# 2pix.net
KiCad netlist of a schematic drawn in EAGLE
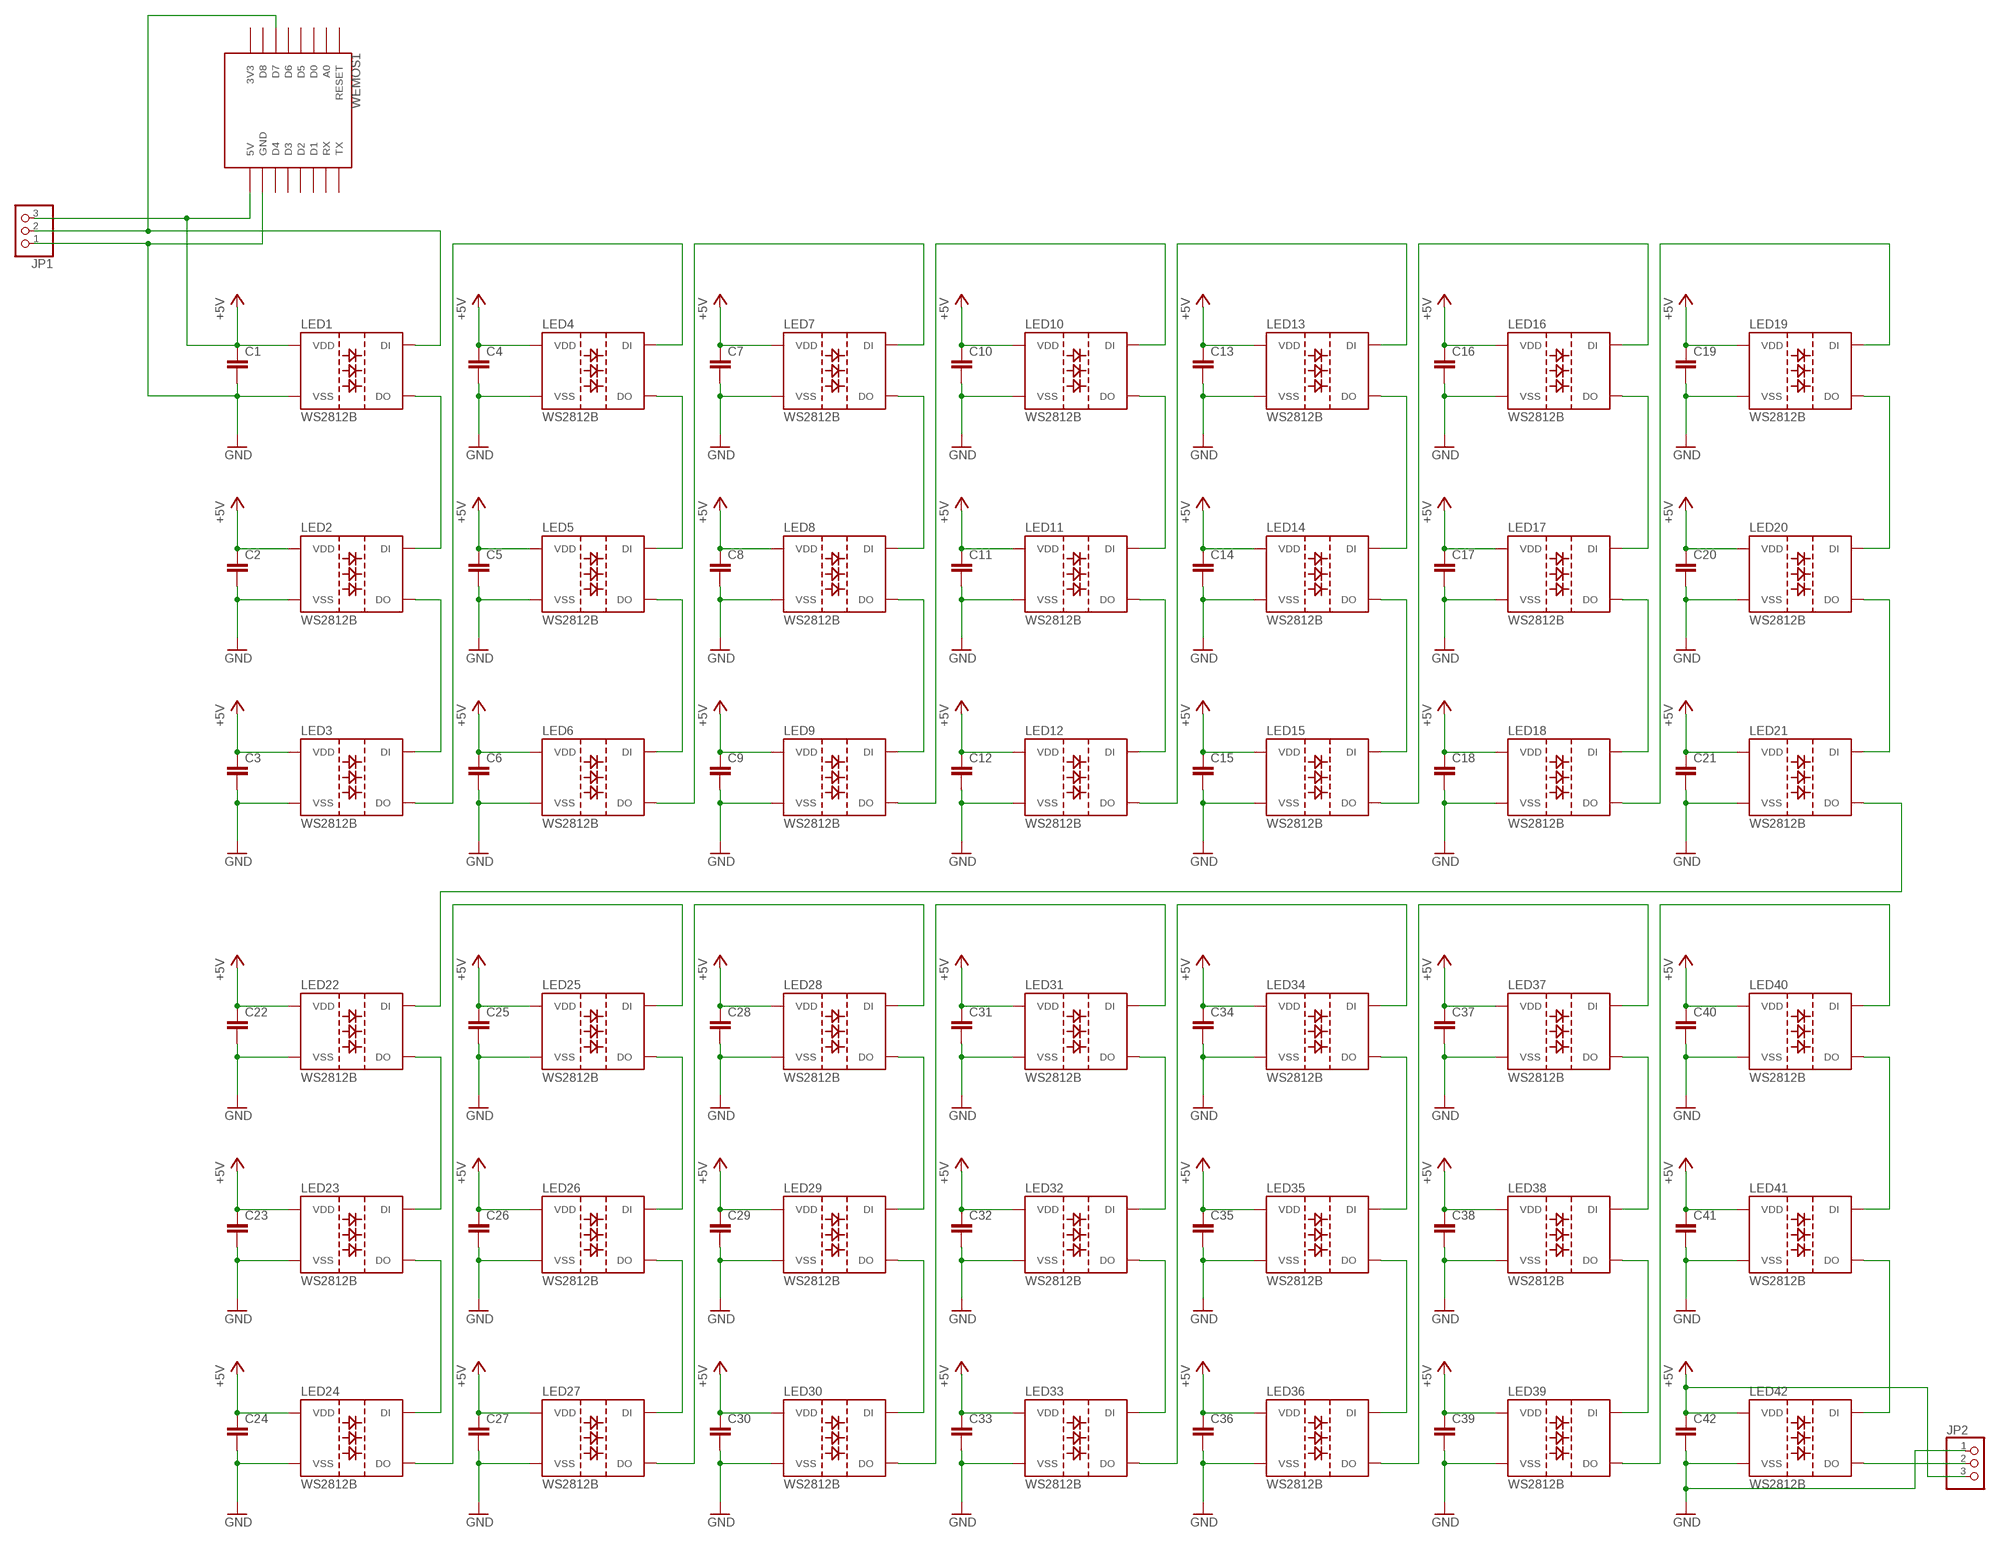
[diagram p0: schematic, sheet 1]

(export (version "E")
  (design (tool "Eeschema 10.0.6"))
  (components
    (comp (ref "C1")
      (value "C-EUC1206")
      (footprint "eagle-import:C1206")
      (libsource (lib "eagle-import") (part "C-EUC1206"))
    )
    (comp (ref "C2")
      (value "C-EUC1206")
      (footprint "eagle-import:C1206")
      (libsource (lib "eagle-import") (part "C-EUC1206"))
    )
    (comp (ref "C3")
      (value "C-EUC1206")
      (footprint "eagle-import:C1206")
      (libsource (lib "eagle-import") (part "C-EUC1206"))
    )
    (comp (ref "C4")
      (value "C-EUC1206")
      (footprint "eagle-import:C1206")
      (libsource (lib "eagle-import") (part "C-EUC1206"))
    )
    (comp (ref "C5")
      (value "C-EUC1206")
      (footprint "eagle-import:C1206")
      (libsource (lib "eagle-import") (part "C-EUC1206"))
    )
    (comp (ref "C6")
      (value "C-EUC1206")
      (footprint "eagle-import:C1206")
      (libsource (lib "eagle-import") (part "C-EUC1206"))
    )
    (comp (ref "C7")
      (value "C-EUC1206")
      (footprint "eagle-import:C1206")
      (libsource (lib "eagle-import") (part "C-EUC1206"))
    )
    (comp (ref "C8")
      (value "C-EUC1206")
      (footprint "eagle-import:C1206")
      (libsource (lib "eagle-import") (part "C-EUC1206"))
    )
    (comp (ref "C9")
      (value "C-EUC1206")
      (footprint "eagle-import:C1206")
      (libsource (lib "eagle-import") (part "C-EUC1206"))
    )
    (comp (ref "C10")
      (value "C-EUC1206")
      (footprint "eagle-import:C1206")
      (libsource (lib "eagle-import") (part "C-EUC1206"))
    )
    (comp (ref "C11")
      (value "C-EUC1206")
      (footprint "eagle-import:C1206")
      (libsource (lib "eagle-import") (part "C-EUC1206"))
    )
    (comp (ref "C12")
      (value "C-EUC1206")
      (footprint "eagle-import:C1206")
      (libsource (lib "eagle-import") (part "C-EUC1206"))
    )
    (comp (ref "C13")
      (value "C-EUC1206")
      (footprint "eagle-import:C1206")
      (libsource (lib "eagle-import") (part "C-EUC1206"))
    )
    (comp (ref "C14")
      (value "C-EUC1206")
      (footprint "eagle-import:C1206")
      (libsource (lib "eagle-import") (part "C-EUC1206"))
    )
    (comp (ref "C15")
      (value "C-EUC1206")
      (footprint "eagle-import:C1206")
      (libsource (lib "eagle-import") (part "C-EUC1206"))
    )
    (comp (ref "C16")
      (value "C-EUC1206")
      (footprint "eagle-import:C1206")
      (libsource (lib "eagle-import") (part "C-EUC1206"))
    )
    (comp (ref "C17")
      (value "C-EUC1206")
      (footprint "eagle-import:C1206")
      (libsource (lib "eagle-import") (part "C-EUC1206"))
    )
    (comp (ref "C18")
      (value "C-EUC1206")
      (footprint "eagle-import:C1206")
      (libsource (lib "eagle-import") (part "C-EUC1206"))
    )
    (comp (ref "C19")
      (value "C-EUC1206")
      (footprint "eagle-import:C1206")
      (libsource (lib "eagle-import") (part "C-EUC1206"))
    )
    (comp (ref "C20")
      (value "C-EUC1206")
      (footprint "eagle-import:C1206")
      (libsource (lib "eagle-import") (part "C-EUC1206"))
    )
    (comp (ref "C21")
      (value "C-EUC1206")
      (footprint "eagle-import:C1206")
      (libsource (lib "eagle-import") (part "C-EUC1206"))
    )
    (comp (ref "C22")
      (value "C-EUC1206")
      (footprint "eagle-import:C1206")
      (libsource (lib "eagle-import") (part "C-EUC1206"))
    )
    (comp (ref "C23")
      (value "C-EUC1206")
      (footprint "eagle-import:C1206")
      (libsource (lib "eagle-import") (part "C-EUC1206"))
    )
    (comp (ref "C24")
      (value "C-EUC1206")
      (footprint "eagle-import:C1206")
      (libsource (lib "eagle-import") (part "C-EUC1206"))
    )
    (comp (ref "C25")
      (value "C-EUC1206")
      (footprint "eagle-import:C1206")
      (libsource (lib "eagle-import") (part "C-EUC1206"))
    )
    (comp (ref "C26")
      (value "C-EUC1206")
      (footprint "eagle-import:C1206")
      (libsource (lib "eagle-import") (part "C-EUC1206"))
    )
    (comp (ref "C27")
      (value "C-EUC1206")
      (footprint "eagle-import:C1206")
      (libsource (lib "eagle-import") (part "C-EUC1206"))
    )
    (comp (ref "C28")
      (value "C-EUC1206")
      (footprint "eagle-import:C1206")
      (libsource (lib "eagle-import") (part "C-EUC1206"))
    )
    (comp (ref "C29")
      (value "C-EUC1206")
      (footprint "eagle-import:C1206")
      (libsource (lib "eagle-import") (part "C-EUC1206"))
    )
    (comp (ref "C30")
      (value "C-EUC1206")
      (footprint "eagle-import:C1206")
      (libsource (lib "eagle-import") (part "C-EUC1206"))
    )
    (comp (ref "C31")
      (value "C-EUC1206")
      (footprint "eagle-import:C1206")
      (libsource (lib "eagle-import") (part "C-EUC1206"))
    )
    (comp (ref "C32")
      (value "C-EUC1206")
      (footprint "eagle-import:C1206")
      (libsource (lib "eagle-import") (part "C-EUC1206"))
    )
    (comp (ref "C33")
      (value "C-EUC1206")
      (footprint "eagle-import:C1206")
      (libsource (lib "eagle-import") (part "C-EUC1206"))
    )
    (comp (ref "C34")
      (value "C-EUC1206")
      (footprint "eagle-import:C1206")
      (libsource (lib "eagle-import") (part "C-EUC1206"))
    )
    (comp (ref "C35")
      (value "C-EUC1206")
      (footprint "eagle-import:C1206")
      (libsource (lib "eagle-import") (part "C-EUC1206"))
    )
    (comp (ref "C36")
      (value "C-EUC1206")
      (footprint "eagle-import:C1206")
      (libsource (lib "eagle-import") (part "C-EUC1206"))
    )
    (comp (ref "C37")
      (value "C-EUC1206")
      (footprint "eagle-import:C1206")
      (libsource (lib "eagle-import") (part "C-EUC1206"))
    )
    (comp (ref "C38")
      (value "C-EUC1206")
      (footprint "eagle-import:C1206")
      (libsource (lib "eagle-import") (part "C-EUC1206"))
    )
    (comp (ref "C39")
      (value "C-EUC1206")
      (footprint "eagle-import:C1206")
      (libsource (lib "eagle-import") (part "C-EUC1206"))
    )
    (comp (ref "C40")
      (value "C-EUC1206")
      (footprint "eagle-import:C1206")
      (libsource (lib "eagle-import") (part "C-EUC1206"))
    )
    (comp (ref "C41")
      (value "C-EUC1206")
      (footprint "eagle-import:C1206")
      (libsource (lib "eagle-import") (part "C-EUC1206"))
    )
    (comp (ref "C42")
      (value "C-EUC1206")
      (footprint "eagle-import:C1206")
      (libsource (lib "eagle-import") (part "C-EUC1206"))
    )
    (comp (ref "JP1")
      (value "PINHD-1X3")
      (footprint "eagle-import:1X03")
      (libsource (lib "eagle-import") (part "PINHD-1X3"))
    )
    (comp (ref "JP2")
      (value "PINHD-1X3")
      (footprint "eagle-import:1X03")
      (libsource (lib "eagle-import") (part "PINHD-1X3"))
    )
    (comp (ref "LED1")
      (value "WS2812B")
      (footprint "eagle-import:WS2812B")
      (libsource (lib "eagle-import") (part "WS2812B"))
    )
    (comp (ref "LED2")
      (value "WS2812B")
      (footprint "eagle-import:WS2812B")
      (libsource (lib "eagle-import") (part "WS2812B"))
    )
    (comp (ref "LED3")
      (value "WS2812B")
      (footprint "eagle-import:WS2812B")
      (libsource (lib "eagle-import") (part "WS2812B"))
    )
    (comp (ref "LED4")
      (value "WS2812B")
      (footprint "eagle-import:WS2812B")
      (libsource (lib "eagle-import") (part "WS2812B"))
    )
    (comp (ref "LED5")
      (value "WS2812B")
      (footprint "eagle-import:WS2812B")
      (libsource (lib "eagle-import") (part "WS2812B"))
    )
    (comp (ref "LED6")
      (value "WS2812B")
      (footprint "eagle-import:WS2812B")
      (libsource (lib "eagle-import") (part "WS2812B"))
    )
    (comp (ref "LED7")
      (value "WS2812B")
      (footprint "eagle-import:WS2812B")
      (libsource (lib "eagle-import") (part "WS2812B"))
    )
    (comp (ref "LED8")
      (value "WS2812B")
      (footprint "eagle-import:WS2812B")
      (libsource (lib "eagle-import") (part "WS2812B"))
    )
    (comp (ref "LED9")
      (value "WS2812B")
      (footprint "eagle-import:WS2812B")
      (libsource (lib "eagle-import") (part "WS2812B"))
    )
    (comp (ref "LED10")
      (value "WS2812B")
      (footprint "eagle-import:WS2812B")
      (libsource (lib "eagle-import") (part "WS2812B"))
    )
    (comp (ref "LED11")
      (value "WS2812B")
      (footprint "eagle-import:WS2812B")
      (libsource (lib "eagle-import") (part "WS2812B"))
    )
    (comp (ref "LED12")
      (value "WS2812B")
      (footprint "eagle-import:WS2812B")
      (libsource (lib "eagle-import") (part "WS2812B"))
    )
    (comp (ref "LED13")
      (value "WS2812B")
      (footprint "eagle-import:WS2812B")
      (libsource (lib "eagle-import") (part "WS2812B"))
    )
    (comp (ref "LED14")
      (value "WS2812B")
      (footprint "eagle-import:WS2812B")
      (libsource (lib "eagle-import") (part "WS2812B"))
    )
    (comp (ref "LED15")
      (value "WS2812B")
      (footprint "eagle-import:WS2812B")
      (libsource (lib "eagle-import") (part "WS2812B"))
    )
    (comp (ref "LED16")
      (value "WS2812B")
      (footprint "eagle-import:WS2812B")
      (libsource (lib "eagle-import") (part "WS2812B"))
    )
    (comp (ref "LED17")
      (value "WS2812B")
      (footprint "eagle-import:WS2812B")
      (libsource (lib "eagle-import") (part "WS2812B"))
    )
    (comp (ref "LED18")
      (value "WS2812B")
      (footprint "eagle-import:WS2812B")
      (libsource (lib "eagle-import") (part "WS2812B"))
    )
    (comp (ref "LED19")
      (value "WS2812B")
      (footprint "eagle-import:WS2812B")
      (libsource (lib "eagle-import") (part "WS2812B"))
    )
    (comp (ref "LED20")
      (value "WS2812B")
      (footprint "eagle-import:WS2812B")
      (libsource (lib "eagle-import") (part "WS2812B"))
    )
    (comp (ref "LED21")
      (value "WS2812B")
      (footprint "eagle-import:WS2812B")
      (libsource (lib "eagle-import") (part "WS2812B"))
    )
    (comp (ref "LED22")
      (value "WS2812B")
      (footprint "eagle-import:WS2812B")
      (libsource (lib "eagle-import") (part "WS2812B"))
    )
    (comp (ref "LED23")
      (value "WS2812B")
      (footprint "eagle-import:WS2812B")
      (libsource (lib "eagle-import") (part "WS2812B"))
    )
    (comp (ref "LED24")
      (value "WS2812B")
      (footprint "eagle-import:WS2812B")
      (libsource (lib "eagle-import") (part "WS2812B"))
    )
    (comp (ref "LED25")
      (value "WS2812B")
      (footprint "eagle-import:WS2812B")
      (libsource (lib "eagle-import") (part "WS2812B"))
    )
    (comp (ref "LED26")
      (value "WS2812B")
      (footprint "eagle-import:WS2812B")
      (libsource (lib "eagle-import") (part "WS2812B"))
    )
    (comp (ref "LED27")
      (value "WS2812B")
      (footprint "eagle-import:WS2812B")
      (libsource (lib "eagle-import") (part "WS2812B"))
    )
    (comp (ref "LED28")
      (value "WS2812B")
      (footprint "eagle-import:WS2812B")
      (libsource (lib "eagle-import") (part "WS2812B"))
    )
    (comp (ref "LED29")
      (value "WS2812B")
      (footprint "eagle-import:WS2812B")
      (libsource (lib "eagle-import") (part "WS2812B"))
    )
    (comp (ref "LED30")
      (value "WS2812B")
      (footprint "eagle-import:WS2812B")
      (libsource (lib "eagle-import") (part "WS2812B"))
    )
    (comp (ref "LED31")
      (value "WS2812B")
      (footprint "eagle-import:WS2812B")
      (libsource (lib "eagle-import") (part "WS2812B"))
    )
    (comp (ref "LED32")
      (value "WS2812B")
      (footprint "eagle-import:WS2812B")
      (libsource (lib "eagle-import") (part "WS2812B"))
    )
    (comp (ref "LED33")
      (value "WS2812B")
      (footprint "eagle-import:WS2812B")
      (libsource (lib "eagle-import") (part "WS2812B"))
    )
    (comp (ref "LED34")
      (value "WS2812B")
      (footprint "eagle-import:WS2812B")
      (libsource (lib "eagle-import") (part "WS2812B"))
    )
    (comp (ref "LED35")
      (value "WS2812B")
      (footprint "eagle-import:WS2812B")
      (libsource (lib "eagle-import") (part "WS2812B"))
    )
    (comp (ref "LED36")
      (value "WS2812B")
      (footprint "eagle-import:WS2812B")
      (libsource (lib "eagle-import") (part "WS2812B"))
    )
    (comp (ref "LED37")
      (value "WS2812B")
      (footprint "eagle-import:WS2812B")
      (libsource (lib "eagle-import") (part "WS2812B"))
    )
    (comp (ref "LED38")
      (value "WS2812B")
      (footprint "eagle-import:WS2812B")
      (libsource (lib "eagle-import") (part "WS2812B"))
    )
    (comp (ref "LED39")
      (value "WS2812B")
      (footprint "eagle-import:WS2812B")
      (libsource (lib "eagle-import") (part "WS2812B"))
    )
    (comp (ref "LED40")
      (value "WS2812B")
      (footprint "eagle-import:WS2812B")
      (libsource (lib "eagle-import") (part "WS2812B"))
    )
    (comp (ref "LED41")
      (value "WS2812B")
      (footprint "eagle-import:WS2812B")
      (libsource (lib "eagle-import") (part "WS2812B"))
    )
    (comp (ref "LED42")
      (value "WS2812B")
      (footprint "eagle-import:WS2812B")
      (libsource (lib "eagle-import") (part "WS2812B"))
    )
    (comp (ref "WEMOS1")
      (value "WEMOS-D1-MINI")
      (footprint "eagle-import:WEMOS-D1-MINI")
      (libsource (lib "eagle-import") (part "WEMOS-D1-MINI"))
    )
  )
  (nets
    (net (code "1") (name "+5V") (class "Default")
      (node (ref "C1") (pin "1") (pinfunction "1_1") (pintype "passive"))
      (node (ref "C10") (pin "1") (pinfunction "1_1") (pintype "passive"))
      (node (ref "C11") (pin "1") (pinfunction "1_1") (pintype "passive"))
      (node (ref "C12") (pin "1") (pinfunction "1_1") (pintype "passive"))
      (node (ref "C13") (pin "1") (pinfunction "1_1") (pintype "passive"))
      (node (ref "C14") (pin "1") (pinfunction "1_1") (pintype "passive"))
      (node (ref "C15") (pin "1") (pinfunction "1_1") (pintype "passive"))
      (node (ref "C16") (pin "1") (pinfunction "1_1") (pintype "passive"))
      (node (ref "C17") (pin "1") (pinfunction "1_1") (pintype "passive"))
      (node (ref "C18") (pin "1") (pinfunction "1_1") (pintype "passive"))
      (node (ref "C19") (pin "1") (pinfunction "1_1") (pintype "passive"))
      (node (ref "C2") (pin "1") (pinfunction "1_1") (pintype "passive"))
      (node (ref "C20") (pin "1") (pinfunction "1_1") (pintype "passive"))
      (node (ref "C21") (pin "1") (pinfunction "1_1") (pintype "passive"))
      (node (ref "C22") (pin "1") (pinfunction "1_1") (pintype "passive"))
      (node (ref "C23") (pin "1") (pinfunction "1_1") (pintype "passive"))
      (node (ref "C24") (pin "1") (pinfunction "1_1") (pintype "passive"))
      (node (ref "C25") (pin "1") (pinfunction "1_1") (pintype "passive"))
      (node (ref "C26") (pin "1") (pinfunction "1_1") (pintype "passive"))
      (node (ref "C27") (pin "1") (pinfunction "1_1") (pintype "passive"))
      (node (ref "C28") (pin "1") (pinfunction "1_1") (pintype "passive"))
      (node (ref "C29") (pin "1") (pinfunction "1_1") (pintype "passive"))
      (node (ref "C3") (pin "1") (pinfunction "1_1") (pintype "passive"))
      (node (ref "C30") (pin "1") (pinfunction "1_1") (pintype "passive"))
      (node (ref "C31") (pin "1") (pinfunction "1_1") (pintype "passive"))
      (node (ref "C32") (pin "1") (pinfunction "1_1") (pintype "passive"))
      (node (ref "C33") (pin "1") (pinfunction "1_1") (pintype "passive"))
      (node (ref "C34") (pin "1") (pinfunction "1_1") (pintype "passive"))
      (node (ref "C35") (pin "1") (pinfunction "1_1") (pintype "passive"))
      (node (ref "C36") (pin "1") (pinfunction "1_1") (pintype "passive"))
      (node (ref "C37") (pin "1") (pinfunction "1_1") (pintype "passive"))
      (node (ref "C38") (pin "1") (pinfunction "1_1") (pintype "passive"))
      (node (ref "C39") (pin "1") (pinfunction "1_1") (pintype "passive"))
      (node (ref "C4") (pin "1") (pinfunction "1_1") (pintype "passive"))
      (node (ref "C40") (pin "1") (pinfunction "1_1") (pintype "passive"))
      (node (ref "C41") (pin "1") (pinfunction "1_1") (pintype "passive"))
      (node (ref "C42") (pin "1") (pinfunction "1_1") (pintype "passive"))
      (node (ref "C5") (pin "1") (pinfunction "1_1") (pintype "passive"))
      (node (ref "C6") (pin "1") (pinfunction "1_1") (pintype "passive"))
      (node (ref "C7") (pin "1") (pinfunction "1_1") (pintype "passive"))
      (node (ref "C8") (pin "1") (pinfunction "1_1") (pintype "passive"))
      (node (ref "C9") (pin "1") (pinfunction "1_1") (pintype "passive"))
      (node (ref "JP1") (pin "3") (pinfunction "3_3") (pintype "passive"))
      (node (ref "JP2") (pin "3") (pinfunction "3_3") (pintype "passive"))
      (node (ref "LED1") (pin "1") (pinfunction "VDD_1") (pintype "bidirectional"))
      (node (ref "LED10") (pin "1") (pinfunction "VDD_1") (pintype "bidirectional"))
      (node (ref "LED11") (pin "1") (pinfunction "VDD_1") (pintype "bidirectional"))
      (node (ref "LED12") (pin "1") (pinfunction "VDD_1") (pintype "bidirectional"))
      (node (ref "LED13") (pin "1") (pinfunction "VDD_1") (pintype "bidirectional"))
      (node (ref "LED14") (pin "1") (pinfunction "VDD_1") (pintype "bidirectional"))
      (node (ref "LED15") (pin "1") (pinfunction "VDD_1") (pintype "bidirectional"))
      (node (ref "LED16") (pin "1") (pinfunction "VDD_1") (pintype "bidirectional"))
      (node (ref "LED17") (pin "1") (pinfunction "VDD_1") (pintype "bidirectional"))
      (node (ref "LED18") (pin "1") (pinfunction "VDD_1") (pintype "bidirectional"))
      (node (ref "LED19") (pin "1") (pinfunction "VDD_1") (pintype "bidirectional"))
      (node (ref "LED2") (pin "1") (pinfunction "VDD_1") (pintype "bidirectional"))
      (node (ref "LED20") (pin "1") (pinfunction "VDD_1") (pintype "bidirectional"))
      (node (ref "LED21") (pin "1") (pinfunction "VDD_1") (pintype "bidirectional"))
      (node (ref "LED22") (pin "1") (pinfunction "VDD_1") (pintype "bidirectional"))
      (node (ref "LED23") (pin "1") (pinfunction "VDD_1") (pintype "bidirectional"))
      (node (ref "LED24") (pin "1") (pinfunction "VDD_1") (pintype "bidirectional"))
      (node (ref "LED25") (pin "1") (pinfunction "VDD_1") (pintype "bidirectional"))
      (node (ref "LED26") (pin "1") (pinfunction "VDD_1") (pintype "bidirectional"))
      (node (ref "LED27") (pin "1") (pinfunction "VDD_1") (pintype "bidirectional"))
      (node (ref "LED28") (pin "1") (pinfunction "VDD_1") (pintype "bidirectional"))
      (node (ref "LED29") (pin "1") (pinfunction "VDD_1") (pintype "bidirectional"))
      (node (ref "LED3") (pin "1") (pinfunction "VDD_1") (pintype "bidirectional"))
      (node (ref "LED30") (pin "1") (pinfunction "VDD_1") (pintype "bidirectional"))
      (node (ref "LED31") (pin "1") (pinfunction "VDD_1") (pintype "bidirectional"))
      (node (ref "LED32") (pin "1") (pinfunction "VDD_1") (pintype "bidirectional"))
      (node (ref "LED33") (pin "1") (pinfunction "VDD_1") (pintype "bidirectional"))
      (node (ref "LED34") (pin "1") (pinfunction "VDD_1") (pintype "bidirectional"))
      (node (ref "LED35") (pin "1") (pinfunction "VDD_1") (pintype "bidirectional"))
      (node (ref "LED36") (pin "1") (pinfunction "VDD_1") (pintype "bidirectional"))
      (node (ref "LED37") (pin "1") (pinfunction "VDD_1") (pintype "bidirectional"))
      (node (ref "LED38") (pin "1") (pinfunction "VDD_1") (pintype "bidirectional"))
      (node (ref "LED39") (pin "1") (pinfunction "VDD_1") (pintype "bidirectional"))
      (node (ref "LED4") (pin "1") (pinfunction "VDD_1") (pintype "bidirectional"))
      (node (ref "LED40") (pin "1") (pinfunction "VDD_1") (pintype "bidirectional"))
      (node (ref "LED41") (pin "1") (pinfunction "VDD_1") (pintype "bidirectional"))
      (node (ref "LED42") (pin "1") (pinfunction "VDD_1") (pintype "bidirectional"))
      (node (ref "LED5") (pin "1") (pinfunction "VDD_1") (pintype "bidirectional"))
      (node (ref "LED6") (pin "1") (pinfunction "VDD_1") (pintype "bidirectional"))
      (node (ref "LED7") (pin "1") (pinfunction "VDD_1") (pintype "bidirectional"))
      (node (ref "LED8") (pin "1") (pinfunction "VDD_1") (pintype "bidirectional"))
      (node (ref "LED9") (pin "1") (pinfunction "VDD_1") (pintype "bidirectional"))
      (node (ref "WEMOS1") (pin "5V") (pinfunction "5V_5V") (pintype "bidirectional"))
    )
    (net (code "2") (name "GND") (class "Default")
      (node (ref "C1") (pin "2") (pinfunction "2_2") (pintype "passive"))
      (node (ref "C10") (pin "2") (pinfunction "2_2") (pintype "passive"))
      (node (ref "C11") (pin "2") (pinfunction "2_2") (pintype "passive"))
      (node (ref "C12") (pin "2") (pinfunction "2_2") (pintype "passive"))
      (node (ref "C13") (pin "2") (pinfunction "2_2") (pintype "passive"))
      (node (ref "C14") (pin "2") (pinfunction "2_2") (pintype "passive"))
      (node (ref "C15") (pin "2") (pinfunction "2_2") (pintype "passive"))
      (node (ref "C16") (pin "2") (pinfunction "2_2") (pintype "passive"))
      (node (ref "C17") (pin "2") (pinfunction "2_2") (pintype "passive"))
      (node (ref "C18") (pin "2") (pinfunction "2_2") (pintype "passive"))
      (node (ref "C19") (pin "2") (pinfunction "2_2") (pintype "passive"))
      (node (ref "C2") (pin "2") (pinfunction "2_2") (pintype "passive"))
      (node (ref "C20") (pin "2") (pinfunction "2_2") (pintype "passive"))
      (node (ref "C21") (pin "2") (pinfunction "2_2") (pintype "passive"))
      (node (ref "C22") (pin "2") (pinfunction "2_2") (pintype "passive"))
      (node (ref "C23") (pin "2") (pinfunction "2_2") (pintype "passive"))
      (node (ref "C24") (pin "2") (pinfunction "2_2") (pintype "passive"))
      (node (ref "C25") (pin "2") (pinfunction "2_2") (pintype "passive"))
      (node (ref "C26") (pin "2") (pinfunction "2_2") (pintype "passive"))
      (node (ref "C27") (pin "2") (pinfunction "2_2") (pintype "passive"))
      (node (ref "C28") (pin "2") (pinfunction "2_2") (pintype "passive"))
      (node (ref "C29") (pin "2") (pinfunction "2_2") (pintype "passive"))
      (node (ref "C3") (pin "2") (pinfunction "2_2") (pintype "passive"))
      (node (ref "C30") (pin "2") (pinfunction "2_2") (pintype "passive"))
      (node (ref "C31") (pin "2") (pinfunction "2_2") (pintype "passive"))
      (node (ref "C32") (pin "2") (pinfunction "2_2") (pintype "passive"))
      (node (ref "C33") (pin "2") (pinfunction "2_2") (pintype "passive"))
      (node (ref "C34") (pin "2") (pinfunction "2_2") (pintype "passive"))
      (node (ref "C35") (pin "2") (pinfunction "2_2") (pintype "passive"))
      (node (ref "C36") (pin "2") (pinfunction "2_2") (pintype "passive"))
      (node (ref "C37") (pin "2") (pinfunction "2_2") (pintype "passive"))
      (node (ref "C38") (pin "2") (pinfunction "2_2") (pintype "passive"))
      (node (ref "C39") (pin "2") (pinfunction "2_2") (pintype "passive"))
      (node (ref "C4") (pin "2") (pinfunction "2_2") (pintype "passive"))
      (node (ref "C40") (pin "2") (pinfunction "2_2") (pintype "passive"))
      (node (ref "C41") (pin "2") (pinfunction "2_2") (pintype "passive"))
      (node (ref "C42") (pin "2") (pinfunction "2_2") (pintype "passive"))
      (node (ref "C5") (pin "2") (pinfunction "2_2") (pintype "passive"))
      (node (ref "C6") (pin "2") (pinfunction "2_2") (pintype "passive"))
      (node (ref "C7") (pin "2") (pinfunction "2_2") (pintype "passive"))
      (node (ref "C8") (pin "2") (pinfunction "2_2") (pintype "passive"))
      (node (ref "C9") (pin "2") (pinfunction "2_2") (pintype "passive"))
      (node (ref "JP1") (pin "1") (pinfunction "1_1") (pintype "passive"))
      (node (ref "JP2") (pin "1") (pinfunction "1_1") (pintype "passive"))
      (node (ref "LED1") (pin "3") (pinfunction "VSS_3") (pintype "bidirectional"))
      (node (ref "LED10") (pin "3") (pinfunction "VSS_3") (pintype "bidirectional"))
      (node (ref "LED11") (pin "3") (pinfunction "VSS_3") (pintype "bidirectional"))
      (node (ref "LED12") (pin "3") (pinfunction "VSS_3") (pintype "bidirectional"))
      (node (ref "LED13") (pin "3") (pinfunction "VSS_3") (pintype "bidirectional"))
      (node (ref "LED14") (pin "3") (pinfunction "VSS_3") (pintype "bidirectional"))
      (node (ref "LED15") (pin "3") (pinfunction "VSS_3") (pintype "bidirectional"))
      (node (ref "LED16") (pin "3") (pinfunction "VSS_3") (pintype "bidirectional"))
      (node (ref "LED17") (pin "3") (pinfunction "VSS_3") (pintype "bidirectional"))
      (node (ref "LED18") (pin "3") (pinfunction "VSS_3") (pintype "bidirectional"))
      (node (ref "LED19") (pin "3") (pinfunction "VSS_3") (pintype "bidirectional"))
      (node (ref "LED2") (pin "3") (pinfunction "VSS_3") (pintype "bidirectional"))
      (node (ref "LED20") (pin "3") (pinfunction "VSS_3") (pintype "bidirectional"))
      (node (ref "LED21") (pin "3") (pinfunction "VSS_3") (pintype "bidirectional"))
      (node (ref "LED22") (pin "3") (pinfunction "VSS_3") (pintype "bidirectional"))
      (node (ref "LED23") (pin "3") (pinfunction "VSS_3") (pintype "bidirectional"))
      (node (ref "LED24") (pin "3") (pinfunction "VSS_3") (pintype "bidirectional"))
      (node (ref "LED25") (pin "3") (pinfunction "VSS_3") (pintype "bidirectional"))
      (node (ref "LED26") (pin "3") (pinfunction "VSS_3") (pintype "bidirectional"))
      (node (ref "LED27") (pin "3") (pinfunction "VSS_3") (pintype "bidirectional"))
      (node (ref "LED28") (pin "3") (pinfunction "VSS_3") (pintype "bidirectional"))
      (node (ref "LED29") (pin "3") (pinfunction "VSS_3") (pintype "bidirectional"))
      (node (ref "LED3") (pin "3") (pinfunction "VSS_3") (pintype "bidirectional"))
      (node (ref "LED30") (pin "3") (pinfunction "VSS_3") (pintype "bidirectional"))
      (node (ref "LED31") (pin "3") (pinfunction "VSS_3") (pintype "bidirectional"))
      (node (ref "LED32") (pin "3") (pinfunction "VSS_3") (pintype "bidirectional"))
      (node (ref "LED33") (pin "3") (pinfunction "VSS_3") (pintype "bidirectional"))
      (node (ref "LED34") (pin "3") (pinfunction "VSS_3") (pintype "bidirectional"))
      (node (ref "LED35") (pin "3") (pinfunction "VSS_3") (pintype "bidirectional"))
      (node (ref "LED36") (pin "3") (pinfunction "VSS_3") (pintype "bidirectional"))
      (node (ref "LED37") (pin "3") (pinfunction "VSS_3") (pintype "bidirectional"))
      (node (ref "LED38") (pin "3") (pinfunction "VSS_3") (pintype "bidirectional"))
      (node (ref "LED39") (pin "3") (pinfunction "VSS_3") (pintype "bidirectional"))
      (node (ref "LED4") (pin "3") (pinfunction "VSS_3") (pintype "bidirectional"))
      (node (ref "LED40") (pin "3") (pinfunction "VSS_3") (pintype "bidirectional"))
      (node (ref "LED41") (pin "3") (pinfunction "VSS_3") (pintype "bidirectional"))
      (node (ref "LED42") (pin "3") (pinfunction "VSS_3") (pintype "bidirectional"))
      (node (ref "LED5") (pin "3") (pinfunction "VSS_3") (pintype "bidirectional"))
      (node (ref "LED6") (pin "3") (pinfunction "VSS_3") (pintype "bidirectional"))
      (node (ref "LED7") (pin "3") (pinfunction "VSS_3") (pintype "bidirectional"))
      (node (ref "LED8") (pin "3") (pinfunction "VSS_3") (pintype "bidirectional"))
      (node (ref "LED9") (pin "3") (pinfunction "VSS_3") (pintype "bidirectional"))
      (node (ref "WEMOS1") (pin "GND") (pinfunction "GND_GND") (pintype "bidirectional"))
    )
    (net (code "3") (name "Net-(LED1-DI)") (class "Default")
      (node (ref "JP1") (pin "2") (pinfunction "2_2") (pintype "passive"))
      (node (ref "LED1") (pin "4") (pinfunction "DI_4") (pintype "bidirectional"))
      (node (ref "WEMOS1") (pin "D7") (pinfunction "D7_D7") (pintype "bidirectional"))
    )
    (net (code "4") (name "Net-(LED1-DO)") (class "Default")
      (node (ref "LED1") (pin "2") (pinfunction "DO_2") (pintype "bidirectional"))
      (node (ref "LED2") (pin "4") (pinfunction "DI_4") (pintype "bidirectional"))
    )
    (net (code "5") (name "Net-(LED2-DO)") (class "Default")
      (node (ref "LED2") (pin "2") (pinfunction "DO_2") (pintype "bidirectional"))
      (node (ref "LED3") (pin "4") (pinfunction "DI_4") (pintype "bidirectional"))
    )
    (net (code "6") (name "Net-(LED3-DO)") (class "Default")
      (node (ref "LED3") (pin "2") (pinfunction "DO_2") (pintype "bidirectional"))
      (node (ref "LED4") (pin "4") (pinfunction "DI_4") (pintype "bidirectional"))
    )
    (net (code "7") (name "Net-(LED4-DO)") (class "Default")
      (node (ref "LED4") (pin "2") (pinfunction "DO_2") (pintype "bidirectional"))
      (node (ref "LED5") (pin "4") (pinfunction "DI_4") (pintype "bidirectional"))
    )
    (net (code "8") (name "Net-(LED5-DO)") (class "Default")
      (node (ref "LED5") (pin "2") (pinfunction "DO_2") (pintype "bidirectional"))
      (node (ref "LED6") (pin "4") (pinfunction "DI_4") (pintype "bidirectional"))
    )
    (net (code "9") (name "Net-(LED6-DO)") (class "Default")
      (node (ref "LED6") (pin "2") (pinfunction "DO_2") (pintype "bidirectional"))
      (node (ref "LED7") (pin "4") (pinfunction "DI_4") (pintype "bidirectional"))
    )
    (net (code "10") (name "Net-(LED7-DO)") (class "Default")
      (node (ref "LED7") (pin "2") (pinfunction "DO_2") (pintype "bidirectional"))
      (node (ref "LED8") (pin "4") (pinfunction "DI_4") (pintype "bidirectional"))
    )
    (net (code "11") (name "Net-(LED8-DO)") (class "Default")
      (node (ref "LED8") (pin "2") (pinfunction "DO_2") (pintype "bidirectional"))
      (node (ref "LED9") (pin "4") (pinfunction "DI_4") (pintype "bidirectional"))
    )
    (net (code "12") (name "Net-(LED10-DI)") (class "Default")
      (node (ref "LED10") (pin "4") (pinfunction "DI_4") (pintype "bidirectional"))
      (node (ref "LED9") (pin "2") (pinfunction "DO_2") (pintype "bidirectional"))
    )
    (net (code "13") (name "Net-(LED10-DO)") (class "Default")
      (node (ref "LED10") (pin "2") (pinfunction "DO_2") (pintype "bidirectional"))
      (node (ref "LED11") (pin "4") (pinfunction "DI_4") (pintype "bidirectional"))
    )
    (net (code "14") (name "Net-(LED11-DO)") (class "Default")
      (node (ref "LED11") (pin "2") (pinfunction "DO_2") (pintype "bidirectional"))
      (node (ref "LED12") (pin "4") (pinfunction "DI_4") (pintype "bidirectional"))
    )
    (net (code "15") (name "Net-(LED12-DO)") (class "Default")
      (node (ref "LED12") (pin "2") (pinfunction "DO_2") (pintype "bidirectional"))
      (node (ref "LED13") (pin "4") (pinfunction "DI_4") (pintype "bidirectional"))
    )
    (net (code "16") (name "Net-(LED13-DO)") (class "Default")
      (node (ref "LED13") (pin "2") (pinfunction "DO_2") (pintype "bidirectional"))
      (node (ref "LED14") (pin "4") (pinfunction "DI_4") (pintype "bidirectional"))
    )
    (net (code "17") (name "Net-(LED14-DO)") (class "Default")
      (node (ref "LED14") (pin "2") (pinfunction "DO_2") (pintype "bidirectional"))
      (node (ref "LED15") (pin "4") (pinfunction "DI_4") (pintype "bidirectional"))
    )
    (net (code "18") (name "Net-(LED15-DO)") (class "Default")
      (node (ref "LED15") (pin "2") (pinfunction "DO_2") (pintype "bidirectional"))
      (node (ref "LED16") (pin "4") (pinfunction "DI_4") (pintype "bidirectional"))
    )
    (net (code "19") (name "Net-(LED16-DO)") (class "Default")
      (node (ref "LED16") (pin "2") (pinfunction "DO_2") (pintype "bidirectional"))
      (node (ref "LED17") (pin "4") (pinfunction "DI_4") (pintype "bidirectional"))
    )
    (net (code "20") (name "Net-(LED17-DO)") (class "Default")
      (node (ref "LED17") (pin "2") (pinfunction "DO_2") (pintype "bidirectional"))
      (node (ref "LED18") (pin "4") (pinfunction "DI_4") (pintype "bidirectional"))
    )
    (net (code "21") (name "Net-(LED18-DO)") (class "Default")
      (node (ref "LED18") (pin "2") (pinfunction "DO_2") (pintype "bidirectional"))
      (node (ref "LED19") (pin "4") (pinfunction "DI_4") (pintype "bidirectional"))
    )
    (net (code "22") (name "Net-(LED19-DO)") (class "Default")
      (node (ref "LED19") (pin "2") (pinfunction "DO_2") (pintype "bidirectional"))
      (node (ref "LED20") (pin "4") (pinfunction "DI_4") (pintype "bidirectional"))
    )
    (net (code "23") (name "Net-(LED20-DO)") (class "Default")
      (node (ref "LED20") (pin "2") (pinfunction "DO_2") (pintype "bidirectional"))
      (node (ref "LED21") (pin "4") (pinfunction "DI_4") (pintype "bidirectional"))
    )
    (net (code "24") (name "Net-(LED21-DO)") (class "Default")
      (node (ref "LED21") (pin "2") (pinfunction "DO_2") (pintype "bidirectional"))
      (node (ref "LED22") (pin "4") (pinfunction "DI_4") (pintype "bidirectional"))
    )
    (net (code "25") (name "Net-(LED22-DO)") (class "Default")
      (node (ref "LED22") (pin "2") (pinfunction "DO_2") (pintype "bidirectional"))
      (node (ref "LED23") (pin "4") (pinfunction "DI_4") (pintype "bidirectional"))
    )
    (net (code "26") (name "Net-(LED23-DO)") (class "Default")
      (node (ref "LED23") (pin "2") (pinfunction "DO_2") (pintype "bidirectional"))
      (node (ref "LED24") (pin "4") (pinfunction "DI_4") (pintype "bidirectional"))
    )
    (net (code "27") (name "Net-(LED24-DO)") (class "Default")
      (node (ref "LED24") (pin "2") (pinfunction "DO_2") (pintype "bidirectional"))
      (node (ref "LED25") (pin "4") (pinfunction "DI_4") (pintype "bidirectional"))
    )
    (net (code "28") (name "Net-(LED25-DO)") (class "Default")
      (node (ref "LED25") (pin "2") (pinfunction "DO_2") (pintype "bidirectional"))
      (node (ref "LED26") (pin "4") (pinfunction "DI_4") (pintype "bidirectional"))
    )
    (net (code "29") (name "Net-(LED26-DO)") (class "Default")
      (node (ref "LED26") (pin "2") (pinfunction "DO_2") (pintype "bidirectional"))
      (node (ref "LED27") (pin "4") (pinfunction "DI_4") (pintype "bidirectional"))
    )
    (net (code "30") (name "Net-(LED27-DO)") (class "Default")
      (node (ref "LED27") (pin "2") (pinfunction "DO_2") (pintype "bidirectional"))
      (node (ref "LED28") (pin "4") (pinfunction "DI_4") (pintype "bidirectional"))
    )
    (net (code "31") (name "Net-(LED28-DO)") (class "Default")
      (node (ref "LED28") (pin "2") (pinfunction "DO_2") (pintype "bidirectional"))
      (node (ref "LED29") (pin "4") (pinfunction "DI_4") (pintype "bidirectional"))
    )
    (net (code "32") (name "Net-(LED29-DO)") (class "Default")
      (node (ref "LED29") (pin "2") (pinfunction "DO_2") (pintype "bidirectional"))
      (node (ref "LED30") (pin "4") (pinfunction "DI_4") (pintype "bidirectional"))
    )
    (net (code "33") (name "Net-(LED30-DO)") (class "Default")
      (node (ref "LED30") (pin "2") (pinfunction "DO_2") (pintype "bidirectional"))
      (node (ref "LED31") (pin "4") (pinfunction "DI_4") (pintype "bidirectional"))
    )
    (net (code "34") (name "Net-(LED31-DO)") (class "Default")
      (node (ref "LED31") (pin "2") (pinfunction "DO_2") (pintype "bidirectional"))
      (node (ref "LED32") (pin "4") (pinfunction "DI_4") (pintype "bidirectional"))
    )
    (net (code "35") (name "Net-(LED32-DO)") (class "Default")
      (node (ref "LED32") (pin "2") (pinfunction "DO_2") (pintype "bidirectional"))
      (node (ref "LED33") (pin "4") (pinfunction "DI_4") (pintype "bidirectional"))
    )
    (net (code "36") (name "Net-(LED33-DO)") (class "Default")
      (node (ref "LED33") (pin "2") (pinfunction "DO_2") (pintype "bidirectional"))
      (node (ref "LED34") (pin "4") (pinfunction "DI_4") (pintype "bidirectional"))
    )
    (net (code "37") (name "Net-(LED34-DO)") (class "Default")
      (node (ref "LED34") (pin "2") (pinfunction "DO_2") (pintype "bidirectional"))
      (node (ref "LED35") (pin "4") (pinfunction "DI_4") (pintype "bidirectional"))
    )
    (net (code "38") (name "Net-(LED35-DO)") (class "Default")
      (node (ref "LED35") (pin "2") (pinfunction "DO_2") (pintype "bidirectional"))
      (node (ref "LED36") (pin "4") (pinfunction "DI_4") (pintype "bidirectional"))
    )
    (net (code "39") (name "Net-(LED36-DO)") (class "Default")
      (node (ref "LED36") (pin "2") (pinfunction "DO_2") (pintype "bidirectional"))
      (node (ref "LED37") (pin "4") (pinfunction "DI_4") (pintype "bidirectional"))
    )
    (net (code "40") (name "Net-(LED37-DO)") (class "Default")
      (node (ref "LED37") (pin "2") (pinfunction "DO_2") (pintype "bidirectional"))
      (node (ref "LED38") (pin "4") (pinfunction "DI_4") (pintype "bidirectional"))
    )
    (net (code "41") (name "Net-(LED38-DO)") (class "Default")
      (node (ref "LED38") (pin "2") (pinfunction "DO_2") (pintype "bidirectional"))
      (node (ref "LED39") (pin "4") (pinfunction "DI_4") (pintype "bidirectional"))
    )
    (net (code "42") (name "Net-(LED39-DO)") (class "Default")
      (node (ref "LED39") (pin "2") (pinfunction "DO_2") (pintype "bidirectional"))
      (node (ref "LED40") (pin "4") (pinfunction "DI_4") (pintype "bidirectional"))
    )
    (net (code "43") (name "Net-(LED40-DO)") (class "Default")
      (node (ref "LED40") (pin "2") (pinfunction "DO_2") (pintype "bidirectional"))
      (node (ref "LED41") (pin "4") (pinfunction "DI_4") (pintype "bidirectional"))
    )
    (net (code "44") (name "Net-(LED41-DO)") (class "Default")
      (node (ref "LED41") (pin "2") (pinfunction "DO_2") (pintype "bidirectional"))
      (node (ref "LED42") (pin "4") (pinfunction "DI_4") (pintype "bidirectional"))
    )
    (net (code "45") (name "Net-(LED42-DO)") (class "Default")
      (node (ref "JP2") (pin "2") (pinfunction "2_2") (pintype "passive"))
      (node (ref "LED42") (pin "2") (pinfunction "DO_2") (pintype "bidirectional"))
    )
    (net (code "46") (name "unconnected-(WEMOS1-Pad3V3)") (class "Default")
      (node (ref "WEMOS1") (pin "3V3") (pinfunction "3V3_3V3") (pintype "bidirectional"))
    )
    (net (code "47") (name "unconnected-(WEMOS1-PadA0)") (class "Default")
      (node (ref "WEMOS1") (pin "A0") (pinfunction "A0_A0") (pintype "bidirectional"))
    )
    (net (code "48") (name "unconnected-(WEMOS1-PadD0)") (class "Default")
      (node (ref "WEMOS1") (pin "D0") (pinfunction "D0_D0") (pintype "bidirectional"))
    )
    (net (code "49") (name "unconnected-(WEMOS1-PadD1)") (class "Default")
      (node (ref "WEMOS1") (pin "D1") (pinfunction "D1_D1") (pintype "bidirectional"))
    )
    (net (code "50") (name "unconnected-(WEMOS1-PadD2)") (class "Default")
      (node (ref "WEMOS1") (pin "D2") (pinfunction "D2_D2") (pintype "bidirectional"))
    )
    (net (code "51") (name "unconnected-(WEMOS1-PadD3)") (class "Default")
      (node (ref "WEMOS1") (pin "D3") (pinfunction "D3_D3") (pintype "bidirectional"))
    )
    (net (code "52") (name "unconnected-(WEMOS1-PadD4)") (class "Default")
      (node (ref "WEMOS1") (pin "D4") (pinfunction "D4_D4") (pintype "bidirectional"))
    )
    (net (code "53") (name "unconnected-(WEMOS1-PadD5)") (class "Default")
      (node (ref "WEMOS1") (pin "D5") (pinfunction "D5_D5") (pintype "bidirectional"))
    )
    (net (code "54") (name "unconnected-(WEMOS1-PadD6)") (class "Default")
      (node (ref "WEMOS1") (pin "D6") (pinfunction "D6_D6") (pintype "bidirectional"))
    )
    (net (code "55") (name "unconnected-(WEMOS1-PadD8)") (class "Default")
      (node (ref "WEMOS1") (pin "D8") (pinfunction "D8_D8") (pintype "bidirectional"))
    )
    (net (code "56") (name "unconnected-(WEMOS1-PadRESET)") (class "Default")
      (node (ref "WEMOS1") (pin "RESET") (pinfunction "RESET_RESET") (pintype "bidirectional"))
    )
    (net (code "57") (name "unconnected-(WEMOS1-PadRX)") (class "Default")
      (node (ref "WEMOS1") (pin "RX") (pinfunction "RX_RX") (pintype "bidirectional"))
    )
    (net (code "58") (name "unconnected-(WEMOS1-PadTX)") (class "Default")
      (node (ref "WEMOS1") (pin "TX") (pinfunction "TX_TX") (pintype "bidirectional"))
    )
  )
)
